# esp32-c3.net
KiCad netlist of a schematic drawn in EasyEDA Pro
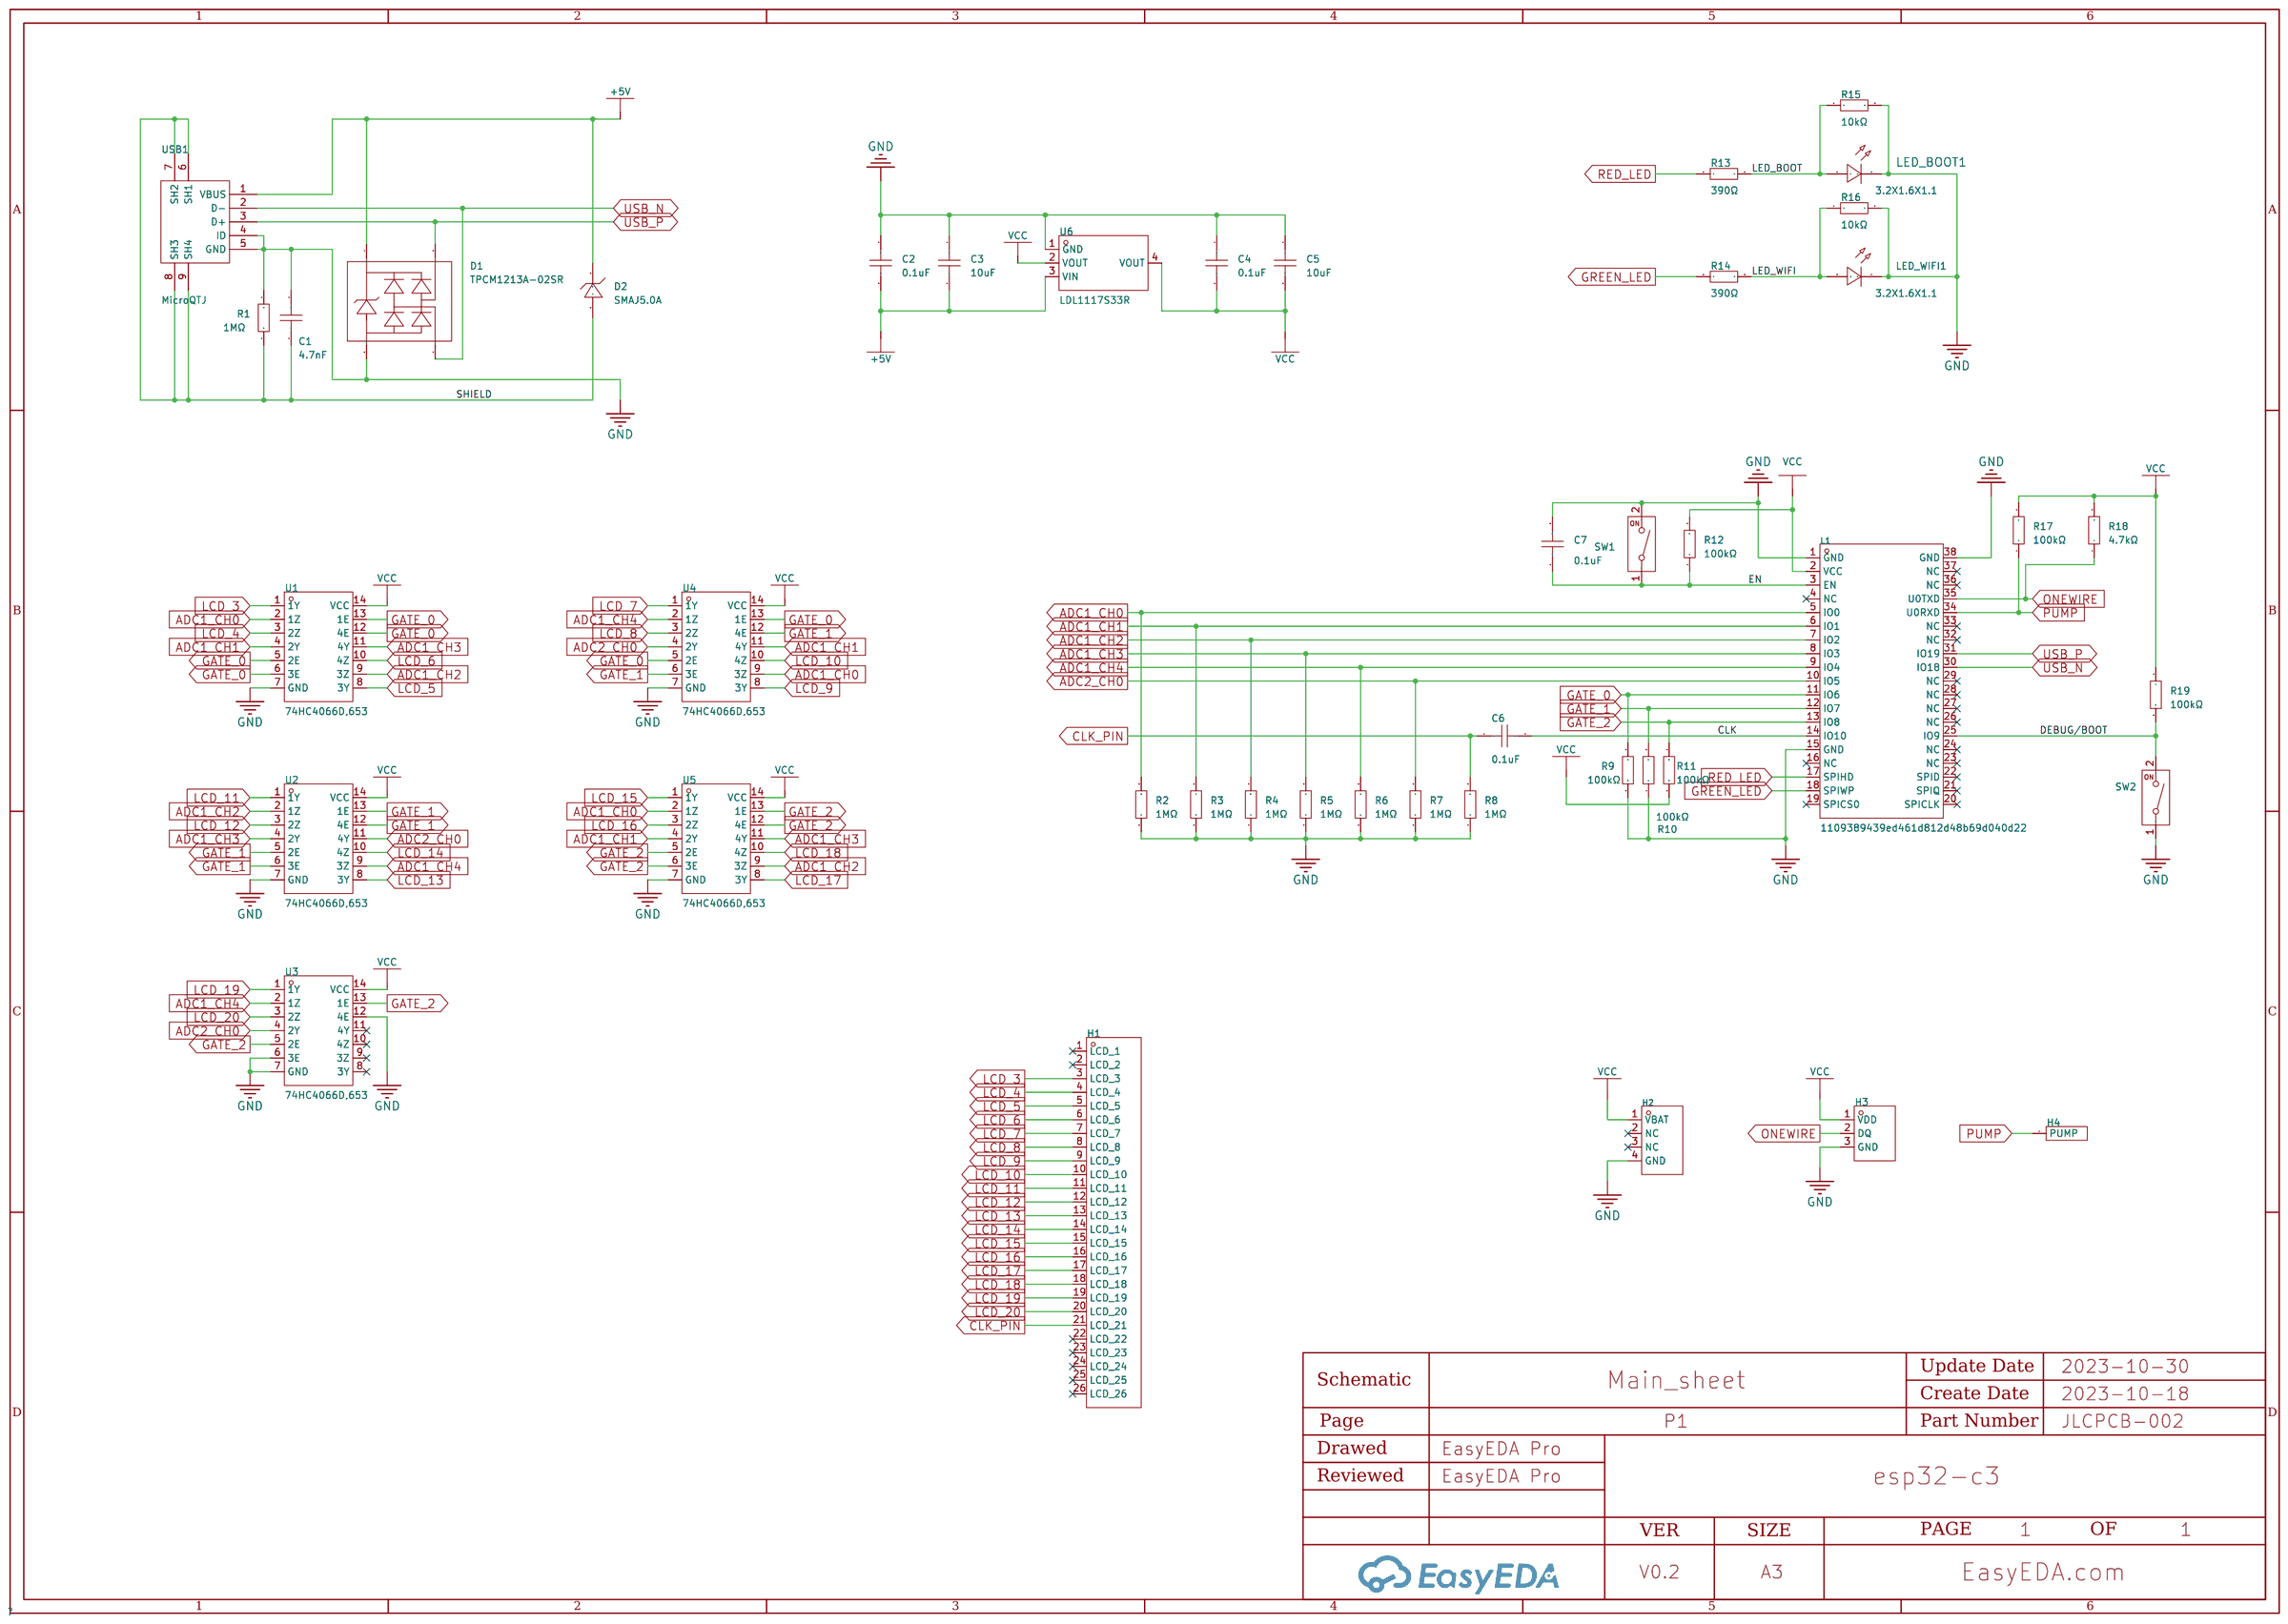
[diagram p0: schematic sheet]

(export (version "E")
  (design (tool "Eeschema 10.0.6"))
  (components
    (comp (ref "C1")
      (value "4.7nF")
      (footprint "easyedapro:C0805")
      (libsource (lib "easyedapro") (part "CAP"))
    )
    (comp (ref "C2")
      (value "0.1uF")
      (footprint "easyedapro:C0805")
      (fields
        (field (name "Manufacturer Part") "CL31B102KGFNNNE")
        (field (name "Manufacturer") "SAMSUNG(三星)")
      )
      (libsource (lib "easyedapro") (part "CAP"))
    )
    (comp (ref "C3")
      (value "10uF")
      (footprint "easyedapro:C0805")
      (fields
        (field (name "Manufacturer Part") "CL31B102KGFNNNE")
        (field (name "Manufacturer") "SAMSUNG(三星)")
      )
      (libsource (lib "easyedapro") (part "CAP"))
    )
    (comp (ref "C4")
      (value "0.1uF")
      (footprint "easyedapro:C0805")
      (fields
        (field (name "Manufacturer Part") "CL31B102KGFNNNE")
        (field (name "Manufacturer") "SAMSUNG(三星)")
      )
      (libsource (lib "easyedapro") (part "CAP"))
    )
    (comp (ref "C5")
      (value "10uF")
      (footprint "easyedapro:C0805")
      (fields
        (field (name "Manufacturer Part") "CL31B102KGFNNNE")
        (field (name "Manufacturer") "SAMSUNG(三星)")
      )
      (libsource (lib "easyedapro") (part "CAP"))
    )
    (comp (ref "C6")
      (value "0.1uF")
      (footprint "easyedapro:C0805")
      (fields
        (field (name "Manufacturer Part") "CL31B102KGFNNNE")
        (field (name "Manufacturer") "SAMSUNG(三星)")
      )
      (libsource (lib "easyedapro") (part "CAP"))
    )
    (comp (ref "C7")
      (value "0.1uF")
      (footprint "easyedapro:C0805")
      (fields
        (field (name "Manufacturer Part") "CL31B102KGFNNNE")
        (field (name "Manufacturer") "SAMSUNG(三星)")
      )
      (libsource (lib "easyedapro") (part "CAP"))
    )
    (comp (ref "D1")
      (value "TPCM1213A-02SR")
      (footprint "easyedapro:SOT-143-4_L2.9-W1.3-P1.90-LS2.4-BL")
      (fields (field (name "Manufacturer") "TECH PUBLIC(台舟)"))
      (libsource (lib "easyedapro") (part "TPCM1213A-02SR"))
    )
    (comp (ref "D2")
      (value "SMAJ5.0A")
      (footprint "easyedapro:SMA_L4.3-W2.6-LS5.2-RD")
      (libsource (lib "easyedapro") (part "SMAJ5.0A-C132575"))
    )
    (comp (ref "H1")
      (value "~")
      (footprint "easyedapro:LCD_26_FOOT")
      (libsource (lib "easyedapro") (part "LCD_26"))
    )
    (comp (ref "H2")
      (value "~")
      (fields (field (name "Manufacturer Part") "PZ254V-11-04P") (field (name "Manufacturer") "XFCN(兴飞)"))
      (libsource (lib "easyedapro") (part "MOTHER_PLATE_CONNECTOR"))
    )
    (comp (ref "H3")
      (value "~")
      (footprint "easyedapro:HDR-TH_3P-P2.54-V-M")
      (libsource (lib "easyedapro") (part "DS18B20_FOOT"))
    )
    (comp (ref "H4")
      (value "~")
      (footprint "easyedapro:HDR-TH_1P-V-M_XKB_X4611WV-01I-C28D40")
      (libsource (lib "easyedapro") (part "PUMP_PIN"))
    )
    (comp (ref "L1")
      (value "2.4GHz")
      (footprint "easyedapro:WIRELM-SMD_ESP-C3-32S-4M")
      (fields
        (field (name "Manufacturer Part") "ESP-C3-32S-2M")
        (field (name "Manufacturer") "Ai-Thinker(安信可)")
      )
      (libsource (lib "easyedapro") (part "ESP-C3-32S-2M"))
    )
    (comp (ref "LED_BOOT1")
      (value "3.2X1.6X1.1")
      (footprint "easyedapro:LED0805-RD_GREEN")
      (libsource (lib "easyedapro") (part "LED_R"))
    )
    (comp (ref "LED_WIFI1")
      (value "3.2X1.6X1.1")
      (footprint "easyedapro:LED0805-RD_GREEN")
      (libsource (lib "easyedapro") (part "LED_G"))
    )
    (comp (ref "R1") (value "1MΩ") (footprint "easyedapro:R1206") (libsource (lib "easyedapro") (part "Res")))
    (comp (ref "R2") (value "1MΩ") (footprint "easyedapro:R1206") (libsource (lib "easyedapro") (part "Res")))
    (comp (ref "R3") (value "1MΩ") (footprint "easyedapro:R1206") (libsource (lib "easyedapro") (part "Res")))
    (comp (ref "R4") (value "1MΩ") (footprint "easyedapro:R1206") (libsource (lib "easyedapro") (part "Res")))
    (comp (ref "R5") (value "1MΩ") (footprint "easyedapro:R1206") (libsource (lib "easyedapro") (part "Res")))
    (comp (ref "R6") (value "1MΩ") (footprint "easyedapro:R1206") (libsource (lib "easyedapro") (part "Res")))
    (comp (ref "R7") (value "1MΩ") (footprint "easyedapro:R1206") (libsource (lib "easyedapro") (part "Res")))
    (comp (ref "R8") (value "1MΩ") (footprint "easyedapro:R1206") (libsource (lib "easyedapro") (part "Res")))
    (comp (ref "R9")
      (value "100kΩ")
      (footprint "easyedapro:R1206")
      (libsource (lib "easyedapro") (part "Res"))
    )
    (comp (ref "R10")
      (value "100kΩ")
      (footprint "easyedapro:R1206")
      (libsource (lib "easyedapro") (part "Res"))
    )
    (comp (ref "R11")
      (value "100kΩ")
      (footprint "easyedapro:R1206")
      (libsource (lib "easyedapro") (part "Res"))
    )
    (comp (ref "R12")
      (value "100kΩ")
      (footprint "easyedapro:R1206")
      (libsource (lib "easyedapro") (part "Res"))
    )
    (comp (ref "R13")
      (value "390Ω")
      (footprint "easyedapro:R1206")
      (libsource (lib "easyedapro") (part "Res"))
    )
    (comp (ref "R14")
      (value "390Ω")
      (footprint "easyedapro:R1206")
      (libsource (lib "easyedapro") (part "Res"))
    )
    (comp (ref "R15")
      (value "10kΩ")
      (footprint "easyedapro:R1206")
      (libsource (lib "easyedapro") (part "Res"))
    )
    (comp (ref "R16")
      (value "10kΩ")
      (footprint "easyedapro:R1206")
      (libsource (lib "easyedapro") (part "Res"))
    )
    (comp (ref "R17")
      (value "100kΩ")
      (footprint "easyedapro:R1206")
      (libsource (lib "easyedapro") (part "Res"))
    )
    (comp (ref "R18")
      (value "4.7kΩ")
      (footprint "easyedapro:R1206")
      (libsource (lib "easyedapro") (part "Res"))
    )
    (comp (ref "R19")
      (value "100kΩ")
      (footprint "easyedapro:R1206")
      (libsource (lib "easyedapro") (part "Res"))
    )
    (comp (ref "SW1")
      (value "RESET")
      (footprint "easyedapro:KEY-SMD_L6.1-W3.7-P7.80-LS8.0")
      (fields
        (field (name "Manufacturer Part") "KAN0441C-0252B1")
        (field (name "Manufacturer") "GANGYUAN(港源)")
      )
      (libsource (lib "easyedapro") (part "KAN0441C-0252B"))
    )
    (comp (ref "SW2")
      (value "BOOT")
      (footprint "easyedapro:KEY-SMD_L6.1-W3.7-P7.80-LS8.0")
      (fields
        (field (name "Manufacturer Part") "KAN0441C-0252B1")
        (field (name "Manufacturer") "GANGYUAN(港源)")
      )
      (libsource (lib "easyedapro") (part "KAN0441C-0252B"))
    )
    (comp (ref "U1")
      (value "74HC4066D,653")
      (footprint "easyedapro:SOIC-14_L8.7-W3.9-P1.27-LS6.0-BL")
      (fields (field (name "Manufacturer") "Nexperia(安世)"))
      (libsource (lib "easyedapro") (part "74HC4066D,653"))
    )
    (comp (ref "U2")
      (value "74HC4066D,653")
      (footprint "easyedapro:SOIC-14_L8.7-W3.9-P1.27-LS6.0-BL")
      (fields (field (name "Manufacturer") "Nexperia(安世)"))
      (libsource (lib "easyedapro") (part "74HC4066D,653"))
    )
    (comp (ref "U3")
      (value "74HC4066D,653")
      (footprint "easyedapro:SOIC-14_L8.7-W3.9-P1.27-LS6.0-BL")
      (fields (field (name "Manufacturer") "Nexperia(安世)"))
      (libsource (lib "easyedapro") (part "74HC4066D,653"))
    )
    (comp (ref "U4")
      (value "74HC4066D,653")
      (footprint "easyedapro:SOIC-14_L8.7-W3.9-P1.27-LS6.0-BL")
      (fields (field (name "Manufacturer") "Nexperia(安世)"))
      (libsource (lib "easyedapro") (part "74HC4066D,653"))
    )
    (comp (ref "U5")
      (value "74HC4066D,653")
      (footprint "easyedapro:SOIC-14_L8.7-W3.9-P1.27-LS6.0-BL")
      (fields (field (name "Manufacturer") "Nexperia(安世)"))
      (libsource (lib "easyedapro") (part "74HC4066D,653"))
    )
    (comp (ref "U6")
      (value "LDL1117S33R")
      (footprint "easyedapro:SOT-223-4_L6.5-W3.5-P2.30-LS7.0-BR")
      (fields (field (name "Manufacturer") "ST(意法半导体)"))
      (libsource (lib "easyedapro") (part "LDL1117S33R"))
    )
    (comp (ref "USB1")
      (value "MicroQTJ")
      (footprint "easyedapro:MICRO-USB-SMD_MICROQTJ")
      (fields (field (name "Manufacturer") "SHOU HAN(首韩)"))
      (libsource (lib "easyedapro") (part "MICROQTJ"))
    )
  )
  (nets
    (net (code "1") (name "+5V") (class "Default")
      (node (ref "C2") (pin "2") (pinfunction "2_2") (pintype "input"))
      (node (ref "C3") (pin "2") (pinfunction "2_2") (pintype "input"))
      (node (ref "D1") (pin "4") (pinfunction "4_4") (pintype "input"))
      (node (ref "D2") (pin "1") (pinfunction "C_1") (pintype "input"))
      (node (ref "U6") (pin "3") (pinfunction "VIN_3") (pintype "input"))
      (node (ref "USB1") (pin "1") (pinfunction "VBUS_1") (pintype "input"))
    )
    (net (code "2") (name "/CLK") (class "Default")
      (node (ref "C6") (pin "2") (pinfunction "2_2") (pintype "input"))
      (node (ref "L1") (pin "14") (pinfunction "IO10_14") (pintype "input"))
    )
    (net (code "3") (name "/DEBUG{slash}BOOT") (class "Default")
      (node (ref "L1") (pin "25") (pinfunction "IO9_25") (pintype "input"))
      (node (ref "R19") (pin "2") (pinfunction "2_2") (pintype "input"))
      (node (ref "SW2") (pin "2") (pinfunction "2_2") (pintype "input"))
    )
    (net (code "4") (name "/EN") (class "Default")
      (node (ref "C7") (pin "1") (pinfunction "1_1") (pintype "input"))
      (node (ref "L1") (pin "3") (pinfunction "EN_3") (pintype "input"))
      (node (ref "R12") (pin "1") (pinfunction "1_1") (pintype "input"))
      (node (ref "SW1") (pin "1") (pinfunction "1_1") (pintype "input"))
    )
    (net (code "5") (name "/LED_BOOT") (class "Default")
      (node (ref "LED_BOOT1") (pin "1") (pinfunction "A_1") (pintype "input"))
      (node (ref "R13") (pin "2") (pinfunction "2_2") (pintype "input"))
      (node (ref "R15") (pin "1") (pinfunction "1_1") (pintype "input"))
    )
    (net (code "6") (name "/LED_WIFI") (class "Default")
      (node (ref "LED_WIFI1") (pin "2") (pinfunction "A_2") (pintype "input"))
      (node (ref "R14") (pin "2") (pinfunction "2_2") (pintype "input"))
      (node (ref "R16") (pin "1") (pinfunction "1_1") (pintype "input"))
    )
    (net (code "7") (name "/SHIELD") (class "Default")
      (node (ref "C1") (pin "2") (pinfunction "2_2") (pintype "input"))
      (node (ref "D2") (pin "2") (pinfunction "A_2") (pintype "input"))
      (node (ref "R1") (pin "2") (pinfunction "2_2") (pintype "input"))
      (node (ref "USB1") (pin "6") (pinfunction "SH1_6") (pintype "input"))
      (node (ref "USB1") (pin "7") (pinfunction "SH2_7") (pintype "input"))
      (node (ref "USB1") (pin "8") (pinfunction "SH3_8") (pintype "input"))
      (node (ref "USB1") (pin "9") (pinfunction "SH4_9") (pintype "input"))
    )
    (net (code "8") (name "ADC1_CH0") (class "Default")
      (node (ref "L1") (pin "5") (pinfunction "IO0_5") (pintype "input"))
      (node (ref "R2") (pin "2") (pinfunction "2_2") (pintype "input"))
      (node (ref "U1") (pin "2") (pinfunction "1Z_2") (pintype "input"))
      (node (ref "U4") (pin "9") (pinfunction "3Z_9") (pintype "input"))
      (node (ref "U5") (pin "2") (pinfunction "1Z_2") (pintype "input"))
    )
    (net (code "9") (name "ADC1_CH1") (class "Default")
      (node (ref "L1") (pin "6") (pinfunction "IO1_6") (pintype "input"))
      (node (ref "R3") (pin "2") (pinfunction "2_2") (pintype "input"))
      (node (ref "U1") (pin "4") (pinfunction "2Y_4") (pintype "input"))
      (node (ref "U4") (pin "11") (pinfunction "4Y_11") (pintype "input"))
      (node (ref "U5") (pin "4") (pinfunction "2Y_4") (pintype "input"))
    )
    (net (code "10") (name "ADC1_CH2") (class "Default")
      (node (ref "L1") (pin "7") (pinfunction "IO2_7") (pintype "input"))
      (node (ref "R4") (pin "2") (pinfunction "2_2") (pintype "input"))
      (node (ref "U1") (pin "9") (pinfunction "3Z_9") (pintype "input"))
      (node (ref "U2") (pin "2") (pinfunction "1Z_2") (pintype "input"))
      (node (ref "U5") (pin "9") (pinfunction "3Z_9") (pintype "input"))
    )
    (net (code "11") (name "ADC1_CH3") (class "Default")
      (node (ref "L1") (pin "8") (pinfunction "IO3_8") (pintype "input"))
      (node (ref "R5") (pin "2") (pinfunction "2_2") (pintype "input"))
      (node (ref "U1") (pin "11") (pinfunction "4Y_11") (pintype "input"))
      (node (ref "U2") (pin "4") (pinfunction "2Y_4") (pintype "input"))
      (node (ref "U5") (pin "11") (pinfunction "4Y_11") (pintype "input"))
    )
    (net (code "12") (name "ADC1_CH4") (class "Default")
      (node (ref "L1") (pin "9") (pinfunction "IO4_9") (pintype "input"))
      (node (ref "R6") (pin "2") (pinfunction "2_2") (pintype "input"))
      (node (ref "U2") (pin "9") (pinfunction "3Z_9") (pintype "input"))
      (node (ref "U3") (pin "2") (pinfunction "1Z_2") (pintype "input"))
      (node (ref "U4") (pin "2") (pinfunction "1Z_2") (pintype "input"))
    )
    (net (code "13") (name "ADC2_CH0") (class "Default")
      (node (ref "L1") (pin "10") (pinfunction "IO5_10") (pintype "input"))
      (node (ref "R7") (pin "2") (pinfunction "2_2") (pintype "input"))
      (node (ref "U2") (pin "11") (pinfunction "4Y_11") (pintype "input"))
      (node (ref "U3") (pin "4") (pinfunction "2Y_4") (pintype "input"))
      (node (ref "U4") (pin "4") (pinfunction "2Y_4") (pintype "input"))
    )
    (net (code "14") (name "CLK_PIN") (class "Default")
      (node (ref "C6") (pin "1") (pinfunction "1_1") (pintype "input"))
      (node (ref "H1") (pin "21") (pinfunction "LCD_21_21") (pintype "input"))
      (node (ref "R8") (pin "2") (pinfunction "2_2") (pintype "input"))
    )
    (net (code "15") (name "GATE_0") (class "Default")
      (node (ref "L1") (pin "11") (pinfunction "IO6_11") (pintype "input"))
      (node (ref "R9") (pin "2") (pinfunction "2_2") (pintype "input"))
      (node (ref "U1") (pin "12") (pinfunction "4E_12") (pintype "input"))
      (node (ref "U1") (pin "13") (pinfunction "1E_13") (pintype "input"))
      (node (ref "U1") (pin "5") (pinfunction "2E_5") (pintype "input"))
      (node (ref "U1") (pin "6") (pinfunction "3E_6") (pintype "input"))
      (node (ref "U4") (pin "13") (pinfunction "1E_13") (pintype "input"))
      (node (ref "U4") (pin "5") (pinfunction "2E_5") (pintype "input"))
    )
    (net (code "16") (name "GATE_1") (class "Default")
      (node (ref "L1") (pin "12") (pinfunction "IO7_12") (pintype "input"))
      (node (ref "R10") (pin "2") (pinfunction "2_2") (pintype "input"))
      (node (ref "U2") (pin "12") (pinfunction "4E_12") (pintype "input"))
      (node (ref "U2") (pin "13") (pinfunction "1E_13") (pintype "input"))
      (node (ref "U2") (pin "5") (pinfunction "2E_5") (pintype "input"))
      (node (ref "U2") (pin "6") (pinfunction "3E_6") (pintype "input"))
      (node (ref "U4") (pin "12") (pinfunction "4E_12") (pintype "input"))
      (node (ref "U4") (pin "6") (pinfunction "3E_6") (pintype "input"))
    )
    (net (code "17") (name "GATE_2") (class "Default")
      (node (ref "L1") (pin "13") (pinfunction "IO8_13") (pintype "input"))
      (node (ref "R11") (pin "2") (pinfunction "2_2") (pintype "input"))
      (node (ref "U3") (pin "13") (pinfunction "1E_13") (pintype "input"))
      (node (ref "U3") (pin "5") (pinfunction "2E_5") (pintype "input"))
      (node (ref "U5") (pin "12") (pinfunction "4E_12") (pintype "input"))
      (node (ref "U5") (pin "13") (pinfunction "1E_13") (pintype "input"))
      (node (ref "U5") (pin "5") (pinfunction "2E_5") (pintype "input"))
      (node (ref "U5") (pin "6") (pinfunction "3E_6") (pintype "input"))
    )
    (net (code "18") (name "GND") (class "Default")
      (node (ref "C1") (pin "1") (pinfunction "1_1") (pintype "input"))
      (node (ref "C2") (pin "1") (pinfunction "1_1") (pintype "input"))
      (node (ref "C3") (pin "1") (pinfunction "1_1") (pintype "input"))
      (node (ref "C4") (pin "1") (pinfunction "1_1") (pintype "input"))
      (node (ref "C5") (pin "1") (pinfunction "1_1") (pintype "input"))
      (node (ref "C7") (pin "2") (pinfunction "2_2") (pintype "input"))
      (node (ref "D1") (pin "1") (pinfunction "1_1") (pintype "input"))
      (node (ref "H2") (pin "4") (pinfunction "GND_4") (pintype "input"))
      (node (ref "H3") (pin "3") (pinfunction "GND_3") (pintype "input"))
      (node (ref "L1") (pin "1") (pinfunction "GND_1") (pintype "input"))
      (node (ref "L1") (pin "15") (pinfunction "GND_15") (pintype "input"))
      (node (ref "L1") (pin "38") (pinfunction "GND_38") (pintype "input"))
      (node (ref "LED_BOOT1") (pin "2") (pinfunction "C_2") (pintype "input"))
      (node (ref "LED_WIFI1") (pin "1") (pinfunction "C_1") (pintype "input"))
      (node (ref "R1") (pin "1") (pinfunction "1_1") (pintype "input"))
      (node (ref "R10") (pin "1") (pinfunction "1_1") (pintype "input"))
      (node (ref "R15") (pin "2") (pinfunction "2_2") (pintype "input"))
      (node (ref "R16") (pin "2") (pinfunction "2_2") (pintype "input"))
      (node (ref "R2") (pin "1") (pinfunction "1_1") (pintype "input"))
      (node (ref "R3") (pin "1") (pinfunction "1_1") (pintype "input"))
      (node (ref "R4") (pin "1") (pinfunction "1_1") (pintype "input"))
      (node (ref "R5") (pin "1") (pinfunction "1_1") (pintype "input"))
      (node (ref "R6") (pin "1") (pinfunction "1_1") (pintype "input"))
      (node (ref "R7") (pin "1") (pinfunction "1_1") (pintype "input"))
      (node (ref "R8") (pin "1") (pinfunction "1_1") (pintype "input"))
      (node (ref "R9") (pin "1") (pinfunction "1_1") (pintype "input"))
      (node (ref "SW1") (pin "2") (pinfunction "2_2") (pintype "input"))
      (node (ref "SW2") (pin "1") (pinfunction "1_1") (pintype "input"))
      (node (ref "U1") (pin "7") (pinfunction "GND_7") (pintype "input"))
      (node (ref "U2") (pin "7") (pinfunction "GND_7") (pintype "input"))
      (node (ref "U3") (pin "12") (pinfunction "4E_12") (pintype "input"))
      (node (ref "U3") (pin "6") (pinfunction "3E_6") (pintype "input"))
      (node (ref "U3") (pin "7") (pinfunction "GND_7") (pintype "input"))
      (node (ref "U4") (pin "7") (pinfunction "GND_7") (pintype "input"))
      (node (ref "U5") (pin "7") (pinfunction "GND_7") (pintype "input"))
      (node (ref "U6") (pin "1") (pinfunction "GND_1") (pintype "input"))
      (node (ref "USB1") (pin "4") (pinfunction "ID_4") (pintype "input"))
      (node (ref "USB1") (pin "5") (pinfunction "GND_5") (pintype "input"))
    )
    (net (code "19") (name "GREEN_LED") (class "Default")
      (node (ref "L1") (pin "18") (pinfunction "SPIWP_18") (pintype "input"))
      (node (ref "R14") (pin "1") (pinfunction "1_1") (pintype "input"))
    )
    (net (code "20") (name "LCD_3") (class "Default")
      (node (ref "H1") (pin "3") (pinfunction "LCD_3_3") (pintype "input"))
      (node (ref "U1") (pin "1") (pinfunction "1Y_1") (pintype "input"))
    )
    (net (code "21") (name "LCD_4") (class "Default")
      (node (ref "H1") (pin "4") (pinfunction "LCD_4_4") (pintype "input"))
      (node (ref "U1") (pin "3") (pinfunction "2Z_3") (pintype "input"))
    )
    (net (code "22") (name "LCD_5") (class "Default")
      (node (ref "H1") (pin "5") (pinfunction "LCD_5_5") (pintype "input"))
      (node (ref "U1") (pin "8") (pinfunction "3Y_8") (pintype "input"))
    )
    (net (code "23") (name "LCD_6") (class "Default")
      (node (ref "H1") (pin "6") (pinfunction "LCD_6_6") (pintype "input"))
      (node (ref "U1") (pin "10") (pinfunction "4Z_10") (pintype "input"))
    )
    (net (code "24") (name "LCD_7") (class "Default")
      (node (ref "H1") (pin "7") (pinfunction "LCD_7_7") (pintype "input"))
      (node (ref "U4") (pin "1") (pinfunction "1Y_1") (pintype "input"))
    )
    (net (code "25") (name "LCD_8") (class "Default")
      (node (ref "H1") (pin "8") (pinfunction "LCD_8_8") (pintype "input"))
      (node (ref "U4") (pin "3") (pinfunction "2Z_3") (pintype "input"))
    )
    (net (code "26") (name "LCD_9") (class "Default")
      (node (ref "H1") (pin "9") (pinfunction "LCD_9_9") (pintype "input"))
      (node (ref "U4") (pin "8") (pinfunction "3Y_8") (pintype "input"))
    )
    (net (code "27") (name "LCD_10") (class "Default")
      (node (ref "H1") (pin "10") (pinfunction "LCD_10_10") (pintype "input"))
      (node (ref "U4") (pin "10") (pinfunction "4Z_10") (pintype "input"))
    )
    (net (code "28") (name "LCD_11") (class "Default")
      (node (ref "H1") (pin "11") (pinfunction "LCD_11_11") (pintype "input"))
      (node (ref "U2") (pin "1") (pinfunction "1Y_1") (pintype "input"))
    )
    (net (code "29") (name "LCD_12") (class "Default")
      (node (ref "H1") (pin "12") (pinfunction "LCD_12_12") (pintype "input"))
      (node (ref "U2") (pin "3") (pinfunction "2Z_3") (pintype "input"))
    )
    (net (code "30") (name "LCD_13") (class "Default")
      (node (ref "H1") (pin "13") (pinfunction "LCD_13_13") (pintype "input"))
      (node (ref "U2") (pin "8") (pinfunction "3Y_8") (pintype "input"))
    )
    (net (code "31") (name "LCD_14") (class "Default")
      (node (ref "H1") (pin "14") (pinfunction "LCD_14_14") (pintype "input"))
      (node (ref "U2") (pin "10") (pinfunction "4Z_10") (pintype "input"))
    )
    (net (code "32") (name "LCD_15") (class "Default")
      (node (ref "H1") (pin "15") (pinfunction "LCD_15_15") (pintype "input"))
      (node (ref "U5") (pin "1") (pinfunction "1Y_1") (pintype "input"))
    )
    (net (code "33") (name "LCD_16") (class "Default")
      (node (ref "H1") (pin "16") (pinfunction "LCD_16_16") (pintype "input"))
      (node (ref "U5") (pin "3") (pinfunction "2Z_3") (pintype "input"))
    )
    (net (code "34") (name "LCD_17") (class "Default")
      (node (ref "H1") (pin "17") (pinfunction "LCD_17_17") (pintype "input"))
      (node (ref "U5") (pin "8") (pinfunction "3Y_8") (pintype "input"))
    )
    (net (code "35") (name "LCD_18") (class "Default")
      (node (ref "H1") (pin "18") (pinfunction "LCD_18_18") (pintype "input"))
      (node (ref "U5") (pin "10") (pinfunction "4Z_10") (pintype "input"))
    )
    (net (code "36") (name "LCD_19") (class "Default")
      (node (ref "H1") (pin "19") (pinfunction "LCD_19_19") (pintype "input"))
      (node (ref "U3") (pin "1") (pinfunction "1Y_1") (pintype "input"))
    )
    (net (code "37") (name "LCD_20") (class "Default")
      (node (ref "H1") (pin "20") (pinfunction "LCD_20_20") (pintype "input"))
      (node (ref "U3") (pin "3") (pinfunction "2Z_3") (pintype "input"))
    )
    (net (code "38") (name "ONEWIRE") (class "Default")
      (node (ref "H3") (pin "2") (pinfunction "DQ_2") (pintype "input"))
      (node (ref "L1") (pin "35") (pinfunction "U0TXD_35") (pintype "input"))
      (node (ref "R18") (pin "1") (pinfunction "1_1") (pintype "input"))
    )
    (net (code "39") (name "PUMP") (class "Default")
      (node (ref "H4") (pin "1") (pinfunction "PUMP_1") (pintype "unspecified"))
      (node (ref "L1") (pin "34") (pinfunction "U0RXD_34") (pintype "input"))
      (node (ref "R17") (pin "1") (pinfunction "1_1") (pintype "input"))
    )
    (net (code "40") (name "RED_LED") (class "Default")
      (node (ref "L1") (pin "17") (pinfunction "SPIHD_17") (pintype "input"))
      (node (ref "R13") (pin "1") (pinfunction "1_1") (pintype "input"))
    )
    (net (code "41") (name "USB_N") (class "Default")
      (node (ref "D1") (pin "2") (pinfunction "2_2") (pintype "input"))
      (node (ref "L1") (pin "30") (pinfunction "IO18_30") (pintype "input"))
      (node (ref "USB1") (pin "2") (pinfunction "D-_2") (pintype "input"))
    )
    (net (code "42") (name "USB_P") (class "Default")
      (node (ref "D1") (pin "3") (pinfunction "3_3") (pintype "input"))
      (node (ref "L1") (pin "31") (pinfunction "IO19_31") (pintype "input"))
      (node (ref "USB1") (pin "3") (pinfunction "D+_3") (pintype "input"))
    )
    (net (code "43") (name "VCC") (class "Default")
      (node (ref "C4") (pin "2") (pinfunction "2_2") (pintype "input"))
      (node (ref "C5") (pin "2") (pinfunction "2_2") (pintype "input"))
      (node (ref "H2") (pin "1") (pinfunction "VBAT_1") (pintype "input"))
      (node (ref "H3") (pin "1") (pinfunction "VDD_1") (pintype "input"))
      (node (ref "L1") (pin "2") (pinfunction "VCC_2") (pintype "input"))
      (node (ref "R11") (pin "1") (pinfunction "1_1") (pintype "input"))
      (node (ref "R12") (pin "2") (pinfunction "2_2") (pintype "input"))
      (node (ref "R17") (pin "2") (pinfunction "2_2") (pintype "input"))
      (node (ref "R18") (pin "2") (pinfunction "2_2") (pintype "input"))
      (node (ref "R19") (pin "1") (pinfunction "1_1") (pintype "input"))
      (node (ref "U1") (pin "14") (pinfunction "VCC_14") (pintype "input"))
      (node (ref "U2") (pin "14") (pinfunction "VCC_14") (pintype "input"))
      (node (ref "U3") (pin "14") (pinfunction "VCC_14") (pintype "input"))
      (node (ref "U4") (pin "14") (pinfunction "VCC_14") (pintype "input"))
      (node (ref "U5") (pin "14") (pinfunction "VCC_14") (pintype "input"))
      (node (ref "U6") (pin "2") (pinfunction "VOUT_2") (pintype "input"))
      (node (ref "U6") (pin "4") (pinfunction "VOUT_4") (pintype "input"))
    )
    (net (code "44") (name "unconnected-(H1-LCD_1-Pad1)") (class "Default")
      (node (ref "H1") (pin "1") (pinfunction "LCD_1_1") (pintype "input+no_connect"))
    )
    (net (code "45") (name "unconnected-(H1-LCD_2-Pad2)") (class "Default")
      (node (ref "H1") (pin "2") (pinfunction "LCD_2_2") (pintype "input+no_connect"))
    )
    (net (code "46") (name "unconnected-(H1-LCD_22-Pad22)") (class "Default")
      (node (ref "H1") (pin "22") (pinfunction "LCD_22_22") (pintype "input+no_connect"))
    )
    (net (code "47") (name "unconnected-(H1-LCD_23-Pad23)") (class "Default")
      (node (ref "H1") (pin "23") (pinfunction "LCD_23_23") (pintype "input+no_connect"))
    )
    (net (code "48") (name "unconnected-(H1-LCD_24-Pad24)") (class "Default")
      (node (ref "H1") (pin "24") (pinfunction "LCD_24_24") (pintype "input+no_connect"))
    )
    (net (code "49") (name "unconnected-(H1-LCD_25-Pad25)") (class "Default")
      (node (ref "H1") (pin "25") (pinfunction "LCD_25_25") (pintype "input+no_connect"))
    )
    (net (code "50") (name "unconnected-(H1-LCD_26-Pad26)") (class "Default")
      (node (ref "H1") (pin "26") (pinfunction "LCD_26_26") (pintype "input+no_connect"))
    )
    (net (code "51") (name "unconnected-(H2-NC-Pad2)") (class "Default")
      (node (ref "H2") (pin "2") (pinfunction "NC_2") (pintype "input+no_connect"))
    )
    (net (code "52") (name "unconnected-(H2-NC-Pad3)") (class "Default")
      (node (ref "H2") (pin "3") (pinfunction "NC_3") (pintype "input+no_connect"))
    )
    (net (code "53") (name "unconnected-(L1-NC-Pad4)") (class "Default")
      (node (ref "L1") (pin "4") (pinfunction "NC_4") (pintype "input+no_connect"))
    )
    (net (code "54") (name "unconnected-(L1-NC-Pad16)") (class "Default")
      (node (ref "L1") (pin "16") (pinfunction "NC_16") (pintype "input+no_connect"))
    )
    (net (code "55") (name "unconnected-(L1-NC-Pad23)") (class "Default")
      (node (ref "L1") (pin "23") (pinfunction "NC_23") (pintype "input+no_connect"))
    )
    (net (code "56") (name "unconnected-(L1-NC-Pad24)") (class "Default")
      (node (ref "L1") (pin "24") (pinfunction "NC_24") (pintype "input+no_connect"))
    )
    (net (code "57") (name "unconnected-(L1-NC-Pad26)") (class "Default")
      (node (ref "L1") (pin "26") (pinfunction "NC_26") (pintype "input+no_connect"))
    )
    (net (code "58") (name "unconnected-(L1-NC-Pad27)") (class "Default")
      (node (ref "L1") (pin "27") (pinfunction "NC_27") (pintype "input+no_connect"))
    )
    (net (code "59") (name "unconnected-(L1-NC-Pad28)") (class "Default")
      (node (ref "L1") (pin "28") (pinfunction "NC_28") (pintype "input+no_connect"))
    )
    (net (code "60") (name "unconnected-(L1-NC-Pad29)") (class "Default")
      (node (ref "L1") (pin "29") (pinfunction "NC_29") (pintype "input+no_connect"))
    )
    (net (code "61") (name "unconnected-(L1-NC-Pad32)") (class "Default")
      (node (ref "L1") (pin "32") (pinfunction "NC_32") (pintype "input+no_connect"))
    )
    (net (code "62") (name "unconnected-(L1-NC-Pad33)") (class "Default")
      (node (ref "L1") (pin "33") (pinfunction "NC_33") (pintype "input+no_connect"))
    )
    (net (code "63") (name "unconnected-(L1-NC-Pad36)") (class "Default")
      (node (ref "L1") (pin "36") (pinfunction "NC_36") (pintype "input+no_connect"))
    )
    (net (code "64") (name "unconnected-(L1-NC-Pad37)") (class "Default")
      (node (ref "L1") (pin "37") (pinfunction "NC_37") (pintype "input+no_connect"))
    )
    (net (code "65") (name "unconnected-(L1-SPICLK-Pad20)") (class "Default")
      (node (ref "L1") (pin "20") (pinfunction "SPICLK_20") (pintype "input+no_connect"))
    )
    (net (code "66") (name "unconnected-(L1-SPICS0-Pad19)") (class "Default")
      (node (ref "L1") (pin "19") (pinfunction "SPICS0_19") (pintype "input+no_connect"))
    )
    (net (code "67") (name "unconnected-(L1-SPID-Pad22)") (class "Default")
      (node (ref "L1") (pin "22") (pinfunction "SPID_22") (pintype "input+no_connect"))
    )
    (net (code "68") (name "unconnected-(L1-SPIQ-Pad21)") (class "Default")
      (node (ref "L1") (pin "21") (pinfunction "SPIQ_21") (pintype "input+no_connect"))
    )
    (net (code "69") (name "unconnected-(U3-3Y-Pad8)") (class "Default")
      (node (ref "U3") (pin "8") (pinfunction "3Y_8") (pintype "input+no_connect"))
    )
    (net (code "70") (name "unconnected-(U3-3Z-Pad9)") (class "Default")
      (node (ref "U3") (pin "9") (pinfunction "3Z_9") (pintype "input+no_connect"))
    )
    (net (code "71") (name "unconnected-(U3-4Y-Pad11)") (class "Default")
      (node (ref "U3") (pin "11") (pinfunction "4Y_11") (pintype "input+no_connect"))
    )
    (net (code "72") (name "unconnected-(U3-4Z-Pad10)") (class "Default")
      (node (ref "U3") (pin "10") (pinfunction "4Z_10") (pintype "input+no_connect"))
    )
  )
)
